# CAN_ProtoBoard_home_th.net
KiCad netlist of a schematic drawn in EAGLE
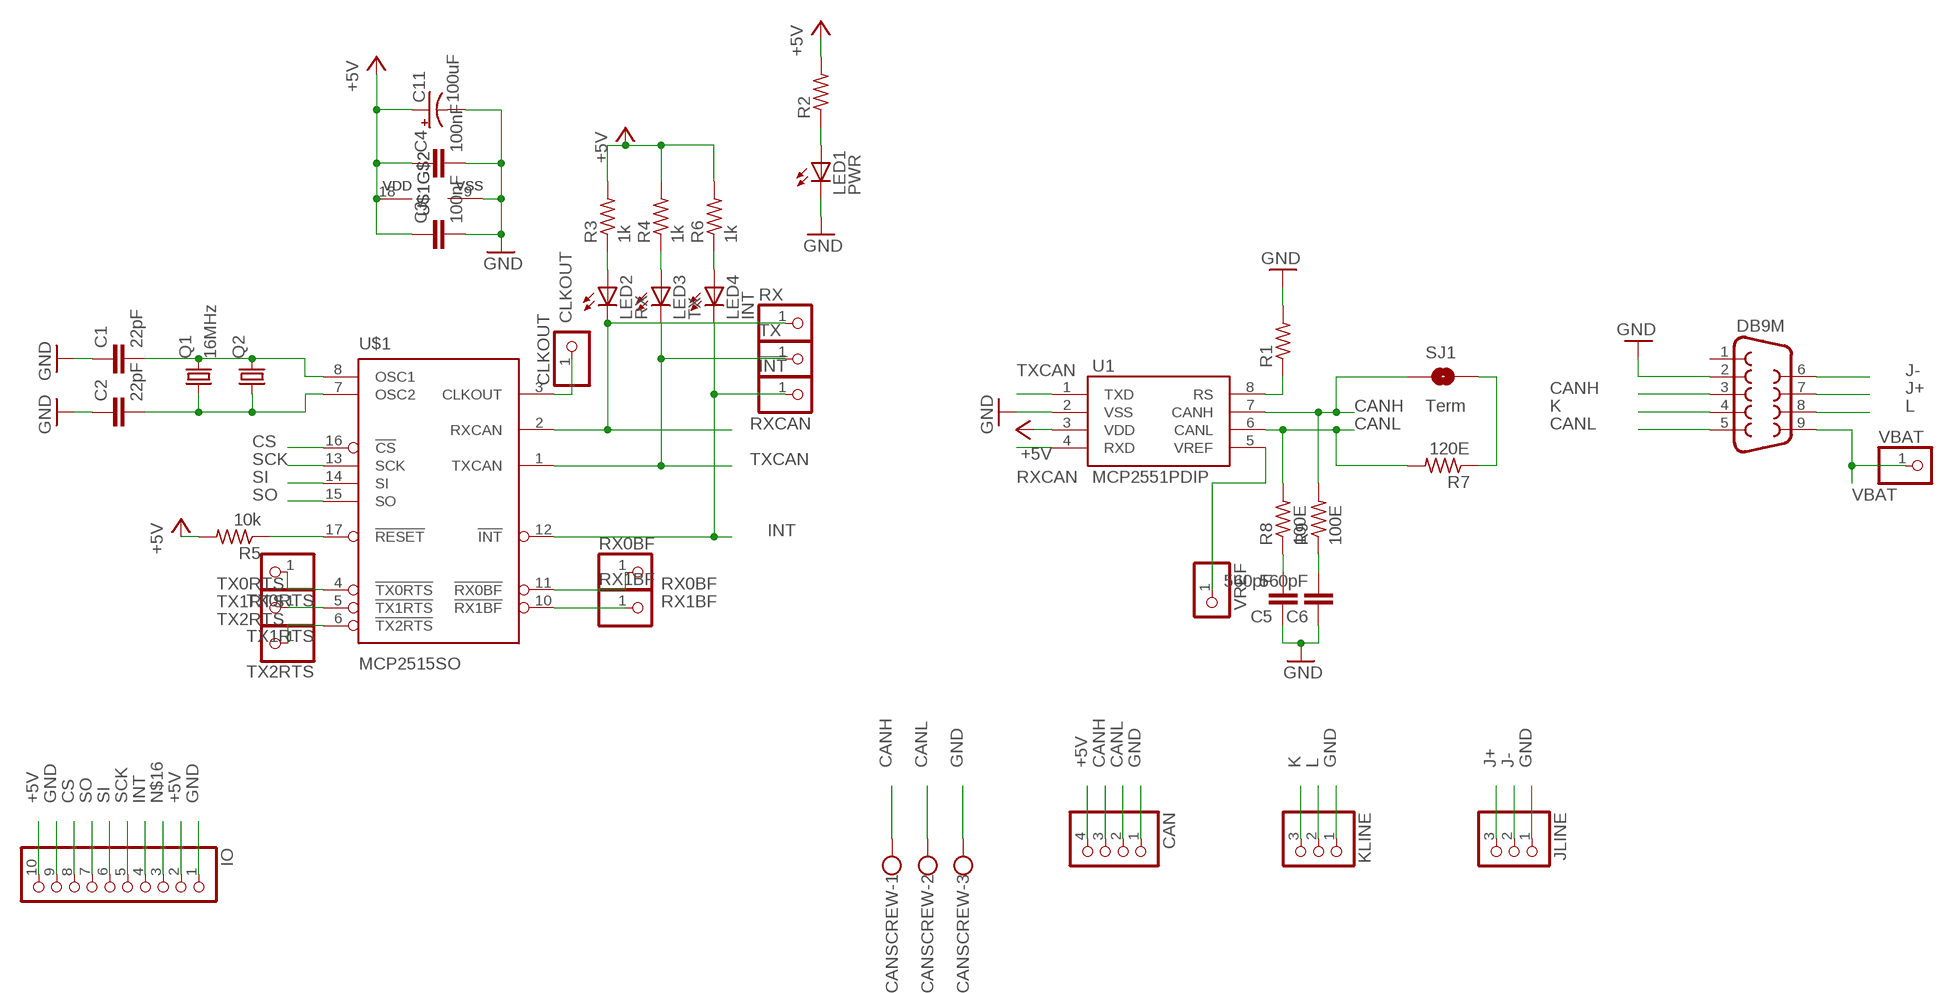
[diagram p0: schematic, sheet 1]

(export (version "E")
  (design (tool "Eeschema 10.0.6"))
  (components
    (comp (ref "!INT")
      (value "PINHD-1X1")
      (footprint "eagle-import:1X01")
      (libsource (lib "eagle-import") (part "PINHD-1X1"))
    )
    (comp (ref "C1")
      (value "22pF")
      (footprint "eagle-import:C0805K")
      (libsource (lib "eagle-import") (part "C-EUC0805K"))
    )
    (comp (ref "C2")
      (value "22pF")
      (footprint "eagle-import:C0805K")
      (libsource (lib "eagle-import") (part "C-EUC0805K"))
    )
    (comp (ref "C3")
      (value "100nF")
      (footprint "eagle-import:C0805K")
      (libsource (lib "eagle-import") (part "C-EUC0805K"))
    )
    (comp (ref "C4")
      (value "100nF")
      (footprint "eagle-import:C0805K")
      (libsource (lib "eagle-import") (part "C-EUC0805K"))
    )
    (comp (ref "C5")
      (value "560pF")
      (footprint "eagle-import:C0805K")
      (libsource (lib "eagle-import") (part "C-EUC0805K"))
    )
    (comp (ref "C6")
      (value "560pF")
      (footprint "eagle-import:C0805K")
      (libsource (lib "eagle-import") (part "C-EUC0805K"))
    )
    (comp (ref "C11")
      (value "100uF")
      (footprint "eagle-import:PANASONIC_D")
      (libsource (lib "eagle-import") (part "CPOL-USD"))
    )
    (comp (ref "CAN")
      (value "PINHD-1X4")
      (footprint "eagle-import:1X04")
      (libsource (lib "eagle-import") (part "PINHD-1X4"))
    )
    (comp (ref "CANSCREW")
      (value "W237-103")
      (footprint "eagle-import:W237-103")
      (fields (field (name "MPN") "237-103"))
      (libsource (lib "eagle-import") (part "W237-103"))
    )
    (comp (ref "CLKOUT")
      (value "PINHD-1X1")
      (footprint "eagle-import:1X01")
      (libsource (lib "eagle-import") (part "PINHD-1X1"))
    )
    (comp (ref "DB9M")
      (value "DB9MALE")
      (footprint "eagle-import:DB9_MALE")
      (libsource (lib "eagle-import") (part "DB9MALE"))
    )
    (comp (ref "IO")
      (value "PINHD-1X10")
      (footprint "eagle-import:1X10")
      (libsource (lib "eagle-import") (part "PINHD-1X10"))
    )
    (comp (ref "JLINE")
      (value "PINHD-1X3")
      (footprint "eagle-import:1X03")
      (libsource (lib "eagle-import") (part "PINHD-1X3"))
    )
    (comp (ref "KLINE")
      (value "PINHD-1X3")
      (footprint "eagle-import:1X03")
      (libsource (lib "eagle-import") (part "PINHD-1X3"))
    )
    (comp (ref "LED1")
      (value "PWR")
      (footprint "eagle-import:CHIPLED_0805")
      (libsource (lib "eagle-import") (part "LEDCHIPLED_0805"))
    )
    (comp (ref "LED2")
      (value "RX")
      (footprint "eagle-import:CHIPLED_0805")
      (libsource (lib "eagle-import") (part "LEDCHIPLED_0805"))
    )
    (comp (ref "LED3")
      (value "TX")
      (footprint "eagle-import:CHIPLED_0805")
      (libsource (lib "eagle-import") (part "LEDCHIPLED_0805"))
    )
    (comp (ref "LED4")
      (value "INT")
      (footprint "eagle-import:CHIPLED_0805")
      (libsource (lib "eagle-import") (part "LEDCHIPLED_0805"))
    )
    (comp (ref "Q1")
      (value "16MHz")
      (footprint "eagle-import:HC49_S")
      (libsource (lib "eagle-import") (part "CRYSTALHC49S"))
    )
    (comp (ref "Q2")
      (value "CRYSTALHC49UP")
      (footprint "eagle-import:HC49UP")
      (libsource (lib "eagle-import") (part "CRYSTALHC49UP"))
    )
    (comp (ref "R1")
      (value "R-US_R0805")
      (footprint "eagle-import:R0805")
      (libsource (lib "eagle-import") (part "R-US_R0805"))
    )
    (comp (ref "R2")
      (value "R-US_R0805")
      (footprint "eagle-import:R0805")
      (libsource (lib "eagle-import") (part "R-US_R0805"))
    )
    (comp (ref "R3")
      (value "1k")
      (footprint "eagle-import:R0805")
      (libsource (lib "eagle-import") (part "R-US_R0805"))
    )
    (comp (ref "R4")
      (value "1k")
      (footprint "eagle-import:R0805")
      (libsource (lib "eagle-import") (part "R-US_R0805"))
    )
    (comp (ref "R5")
      (value "10k")
      (footprint "eagle-import:R0805")
      (libsource (lib "eagle-import") (part "R-US_R0805"))
    )
    (comp (ref "R6")
      (value "1k")
      (footprint "eagle-import:R0805")
      (libsource (lib "eagle-import") (part "R-US_R0805"))
    )
    (comp (ref "R7")
      (value "120E")
      (footprint "eagle-import:R0805")
      (libsource (lib "eagle-import") (part "R-US_R0805"))
    )
    (comp (ref "R8")
      (value "100E")
      (footprint "eagle-import:R0805")
      (libsource (lib "eagle-import") (part "R-US_R0805"))
    )
    (comp (ref "R9")
      (value "100E")
      (footprint "eagle-import:R0805")
      (libsource (lib "eagle-import") (part "R-US_R0805"))
    )
    (comp (ref "RX")
      (value "PINHD-1X1")
      (footprint "eagle-import:1X01")
      (libsource (lib "eagle-import") (part "PINHD-1X1"))
    )
    (comp (ref "RX0BF")
      (value "PINHD-1X1")
      (footprint "eagle-import:1X01")
      (libsource (lib "eagle-import") (part "PINHD-1X1"))
    )
    (comp (ref "RX1BF")
      (value "PINHD-1X1")
      (footprint "eagle-import:1X01")
      (libsource (lib "eagle-import") (part "PINHD-1X1"))
    )
    (comp (ref "SJ1")
      (value "Term")
      (footprint "eagle-import:SJ_2S-TRACE")
      (libsource (lib "eagle-import") (part "SOLDERJUMPERTRACE"))
    )
    (comp (ref "TX")
      (value "PINHD-1X1")
      (footprint "eagle-import:1X01")
      (libsource (lib "eagle-import") (part "PINHD-1X1"))
    )
    (comp (ref "TX0RTS")
      (value "PINHD-1X1")
      (footprint "eagle-import:1X01")
      (libsource (lib "eagle-import") (part "PINHD-1X1"))
    )
    (comp (ref "TX1RTS")
      (value "PINHD-1X1")
      (footprint "eagle-import:1X01")
      (libsource (lib "eagle-import") (part "PINHD-1X1"))
    )
    (comp (ref "TX2RTS")
      (value "PINHD-1X1")
      (footprint "eagle-import:1X01")
      (libsource (lib "eagle-import") (part "PINHD-1X1"))
    )
    (comp (ref "U$1")
      (value "MCP2515SO")
      (footprint "eagle-import:SO-18W")
      (libsource (lib "eagle-import") (part "MCP2515SO"))
    )
    (comp (ref "U1")
      (value "MCP2551PDIP")
      (footprint "eagle-import:DIL08")
      (libsource (lib "eagle-import") (part "MCP2551PDIP"))
    )
    (comp (ref "VBAT")
      (value "PINHD-1X1")
      (footprint "eagle-import:1X01")
      (libsource (lib "eagle-import") (part "PINHD-1X1"))
    )
    (comp (ref "VREF")
      (value "PINHD-1X1")
      (footprint "eagle-import:1X01")
      (libsource (lib "eagle-import") (part "PINHD-1X1"))
    )
  )
  (nets
    (net (code "1") (name "+5V") (class "Default")
      (node (ref "C11") (pin "+") (pinfunction "+_+") (pintype "passive"))
      (node (ref "C3") (pin "1") (pinfunction "1_1") (pintype "passive"))
      (node (ref "C4") (pin "1") (pinfunction "1_1") (pintype "passive"))
      (node (ref "CAN") (pin "4") (pinfunction "4_4") (pintype "passive"))
      (node (ref "IO") (pin "10") (pinfunction "10_10") (pintype "passive"))
      (node (ref "IO") (pin "2") (pinfunction "2_2") (pintype "passive"))
      (node (ref "R2") (pin "2") (pinfunction "2_2") (pintype "passive"))
      (node (ref "R3") (pin "2") (pinfunction "2_2") (pintype "passive"))
      (node (ref "R4") (pin "2") (pinfunction "2_2") (pintype "passive"))
      (node (ref "R5") (pin "2") (pinfunction "2_2") (pintype "passive"))
      (node (ref "R6") (pin "2") (pinfunction "2_2") (pintype "passive"))
      (node (ref "U$1") (pin "18") (pinfunction "VDD_18") (pintype "power_in"))
      (node (ref "U1") (pin "3") (pinfunction "VDD_3") (pintype "bidirectional"))
    )
    (net (code "2") (name "/CANH") (class "Default")
      (node (ref "CAN") (pin "3") (pinfunction "3_3") (pintype "passive"))
      (node (ref "CANSCREW") (pin "1") (pinfunction "KL_1") (pintype "passive"))
      (node (ref "DB9M") (pin "3") (pinfunction "3_3") (pintype "passive"))
      (node (ref "R9") (pin "2") (pinfunction "2_2") (pintype "passive"))
      (node (ref "SJ1") (pin "1") (pinfunction "1_1") (pintype "passive"))
      (node (ref "U1") (pin "7") (pinfunction "CANH_7") (pintype "bidirectional"))
    )
    (net (code "3") (name "/CANL") (class "Default")
      (node (ref "CAN") (pin "2") (pinfunction "2_2") (pintype "passive"))
      (node (ref "CANSCREW") (pin "2") (pinfunction "KL_2") (pintype "passive"))
      (node (ref "DB9M") (pin "5") (pinfunction "5_5") (pintype "passive"))
      (node (ref "R7") (pin "2") (pinfunction "2_2") (pintype "passive"))
      (node (ref "R8") (pin "2") (pinfunction "2_2") (pintype "passive"))
      (node (ref "U1") (pin "6") (pinfunction "CANL_6") (pintype "bidirectional"))
    )
    (net (code "4") (name "/CLKOUT") (class "Default")
      (node (ref "CLKOUT") (pin "1") (pinfunction "1_1") (pintype "passive"))
      (node (ref "U$1") (pin "3") (pinfunction "CLKOUT_3") (pintype "output"))
    )
    (net (code "5") (name "/CS") (class "Default")
      (node (ref "IO") (pin "8") (pinfunction "8_8") (pintype "passive"))
      (node (ref "U$1") (pin "16") (pinfunction "~{CS}_16") (pintype "input"))
    )
    (net (code "6") (name "/INT") (class "Default")
      (node (ref "!INT") (pin "1") (pinfunction "1_1") (pintype "passive"))
      (node (ref "IO") (pin "4") (pinfunction "4_4") (pintype "passive"))
      (node (ref "LED4") (pin "C") (pinfunction "C_C") (pintype "passive"))
      (node (ref "U$1") (pin "12") (pinfunction "~{INT}_12") (pintype "output"))
    )
    (net (code "7") (name "/J+") (class "Default")
      (node (ref "DB9M") (pin "7") (pinfunction "7_7") (pintype "passive"))
      (node (ref "JLINE") (pin "3") (pinfunction "3_3") (pintype "passive"))
    )
    (net (code "8") (name "/J-") (class "Default")
      (node (ref "DB9M") (pin "6") (pinfunction "6_6") (pintype "passive"))
      (node (ref "JLINE") (pin "2") (pinfunction "2_2") (pintype "passive"))
    )
    (net (code "9") (name "/K") (class "Default")
      (node (ref "DB9M") (pin "4") (pinfunction "4_4") (pintype "passive"))
      (node (ref "KLINE") (pin "3") (pinfunction "3_3") (pintype "passive"))
    )
    (net (code "10") (name "/L") (class "Default")
      (node (ref "DB9M") (pin "8") (pinfunction "8_8") (pintype "passive"))
      (node (ref "KLINE") (pin "2") (pinfunction "2_2") (pintype "passive"))
    )
    (net (code "11") (name "/N$16") (class "Default")
      (node (ref "IO") (pin "3") (pinfunction "3_3") (pintype "passive"))
    )
    (net (code "12") (name "/RX0BF") (class "Default")
      (node (ref "RX0BF") (pin "1") (pinfunction "1_1") (pintype "passive"))
      (node (ref "U$1") (pin "11") (pinfunction "~{RX0BF}_11") (pintype "output"))
    )
    (net (code "13") (name "/RX1BF") (class "Default")
      (node (ref "RX1BF") (pin "1") (pinfunction "1_1") (pintype "passive"))
      (node (ref "U$1") (pin "10") (pinfunction "~{RX1BF}_10") (pintype "output"))
    )
    (net (code "14") (name "/RXCAN") (class "Default")
      (node (ref "LED2") (pin "C") (pinfunction "C_C") (pintype "passive"))
      (node (ref "RX") (pin "1") (pinfunction "1_1") (pintype "passive"))
      (node (ref "U$1") (pin "2") (pinfunction "RXCAN_2") (pintype "input"))
      (node (ref "U1") (pin "4") (pinfunction "RXD_4") (pintype "bidirectional"))
    )
    (net (code "15") (name "/SCK") (class "Default")
      (node (ref "IO") (pin "5") (pinfunction "5_5") (pintype "passive"))
      (node (ref "U$1") (pin "13") (pinfunction "SCK_13") (pintype "input"))
    )
    (net (code "16") (name "/SI") (class "Default")
      (node (ref "IO") (pin "6") (pinfunction "6_6") (pintype "passive"))
      (node (ref "U$1") (pin "14") (pinfunction "SI_14") (pintype "input"))
    )
    (net (code "17") (name "/SO") (class "Default")
      (node (ref "IO") (pin "7") (pinfunction "7_7") (pintype "passive"))
      (node (ref "U$1") (pin "15") (pinfunction "SO_15") (pintype "output"))
    )
    (net (code "18") (name "/TX0RTS") (class "Default")
      (node (ref "TX0RTS") (pin "1") (pinfunction "1_1") (pintype "passive"))
      (node (ref "U$1") (pin "4") (pinfunction "~{TX0RTS}_4") (pintype "input"))
    )
    (net (code "19") (name "/TX1RTS") (class "Default")
      (node (ref "TX1RTS") (pin "1") (pinfunction "1_1") (pintype "passive"))
      (node (ref "U$1") (pin "5") (pinfunction "~{TX1RTS}_5") (pintype "input"))
    )
    (net (code "20") (name "/TX2RTS") (class "Default")
      (node (ref "TX2RTS") (pin "1") (pinfunction "1_1") (pintype "passive"))
      (node (ref "U$1") (pin "6") (pinfunction "~{TX2RTS}_6") (pintype "input"))
    )
    (net (code "21") (name "/TXCAN") (class "Default")
      (node (ref "LED3") (pin "C") (pinfunction "C_C") (pintype "passive"))
      (node (ref "TX") (pin "1") (pinfunction "1_1") (pintype "passive"))
      (node (ref "U$1") (pin "1") (pinfunction "TXCAN_1") (pintype "output"))
      (node (ref "U1") (pin "1") (pinfunction "TXD_1") (pintype "bidirectional"))
    )
    (net (code "22") (name "/VBAT") (class "Default")
      (node (ref "DB9M") (pin "9") (pinfunction "9_9") (pintype "passive"))
      (node (ref "VBAT") (pin "1") (pinfunction "1_1") (pintype "passive"))
    )
    (net (code "23") (name "GND") (class "Default")
      (node (ref "C1") (pin "1") (pinfunction "1_1") (pintype "passive"))
      (node (ref "C11") (pin "-") (pinfunction "-_-") (pintype "passive"))
      (node (ref "C2") (pin "1") (pinfunction "1_1") (pintype "passive"))
      (node (ref "C3") (pin "2") (pinfunction "2_2") (pintype "passive"))
      (node (ref "C4") (pin "2") (pinfunction "2_2") (pintype "passive"))
      (node (ref "C5") (pin "1") (pinfunction "1_1") (pintype "passive"))
      (node (ref "C6") (pin "1") (pinfunction "1_1") (pintype "passive"))
      (node (ref "CAN") (pin "1") (pinfunction "1_1") (pintype "passive"))
      (node (ref "CANSCREW") (pin "3") (pinfunction "KL_3") (pintype "passive"))
      (node (ref "DB9M") (pin "2") (pinfunction "2_2") (pintype "passive"))
      (node (ref "IO") (pin "1") (pinfunction "1_1") (pintype "passive"))
      (node (ref "IO") (pin "9") (pinfunction "9_9") (pintype "passive"))
      (node (ref "JLINE") (pin "1") (pinfunction "1_1") (pintype "passive"))
      (node (ref "KLINE") (pin "1") (pinfunction "1_1") (pintype "passive"))
      (node (ref "LED1") (pin "C") (pinfunction "C_C") (pintype "passive"))
      (node (ref "R1") (pin "2") (pinfunction "2_2") (pintype "passive"))
      (node (ref "U$1") (pin "9") (pinfunction "VSS_9") (pintype "power_in"))
      (node (ref "U1") (pin "2") (pinfunction "VSS_2") (pintype "bidirectional"))
    )
    (net (code "24") (name "Net-(C5-Pad2)") (class "Default")
      (node (ref "C5") (pin "2") (pinfunction "2_2") (pintype "passive"))
      (node (ref "R8") (pin "1") (pinfunction "1_1") (pintype "passive"))
    )
    (net (code "25") (name "Net-(C6-Pad2)") (class "Default")
      (node (ref "C6") (pin "2") (pinfunction "2_2") (pintype "passive"))
      (node (ref "R9") (pin "1") (pinfunction "1_1") (pintype "passive"))
    )
    (net (code "26") (name "Net-(LED1-PadA)") (class "Default")
      (node (ref "LED1") (pin "A") (pinfunction "A_A") (pintype "passive"))
      (node (ref "R2") (pin "1") (pinfunction "1_1") (pintype "passive"))
    )
    (net (code "27") (name "Net-(LED2-PadA)") (class "Default")
      (node (ref "LED2") (pin "A") (pinfunction "A_A") (pintype "passive"))
      (node (ref "R3") (pin "1") (pinfunction "1_1") (pintype "passive"))
    )
    (net (code "28") (name "Net-(LED3-PadA)") (class "Default")
      (node (ref "LED3") (pin "A") (pinfunction "A_A") (pintype "passive"))
      (node (ref "R4") (pin "1") (pinfunction "1_1") (pintype "passive"))
    )
    (net (code "29") (name "Net-(LED4-PadA)") (class "Default")
      (node (ref "LED4") (pin "A") (pinfunction "A_A") (pintype "passive"))
      (node (ref "R6") (pin "1") (pinfunction "1_1") (pintype "passive"))
    )
    (net (code "30") (name "Net-(R7-Pad1)") (class "Default")
      (node (ref "R7") (pin "1") (pinfunction "1_1") (pintype "passive"))
      (node (ref "SJ1") (pin "2") (pinfunction "2_2") (pintype "passive"))
    )
    (net (code "31") (name "Net-(U$1A-OSC1)") (class "Default")
      (node (ref "C1") (pin "2") (pinfunction "2_2") (pintype "passive"))
      (node (ref "Q1") (pin "2") (pinfunction "2_2") (pintype "passive"))
      (node (ref "Q2") (pin "2") (pinfunction "2_2") (pintype "passive"))
      (node (ref "U$1") (pin "8") (pinfunction "OSC1_8") (pintype "input"))
    )
    (net (code "32") (name "Net-(U$1A-OSC2)") (class "Default")
      (node (ref "C2") (pin "2") (pinfunction "2_2") (pintype "passive"))
      (node (ref "Q1") (pin "1") (pinfunction "1_1") (pintype "passive"))
      (node (ref "Q2") (pin "1") (pinfunction "1_1") (pintype "passive"))
      (node (ref "U$1") (pin "7") (pinfunction "OSC2_7") (pintype "output"))
    )
    (net (code "33") (name "Net-(U$1A-~{RESET})") (class "Default")
      (node (ref "R5") (pin "1") (pinfunction "1_1") (pintype "passive"))
      (node (ref "U$1") (pin "17") (pinfunction "~{RESET}_17") (pintype "input"))
    )
    (net (code "34") (name "Net-(U1-RS)") (class "Default")
      (node (ref "R1") (pin "1") (pinfunction "1_1") (pintype "passive"))
      (node (ref "U1") (pin "8") (pinfunction "RS_8") (pintype "bidirectional"))
    )
    (net (code "35") (name "Net-(U1-VREF)") (class "Default")
      (node (ref "U1") (pin "5") (pinfunction "VREF_5") (pintype "bidirectional"))
      (node (ref "VREF") (pin "1") (pinfunction "1_1") (pintype "passive"))
    )
    (net (code "36") (name "unconnected-(DB9M-Pad1)") (class "Default")
      (node (ref "DB9M") (pin "1") (pinfunction "1_1") (pintype "passive"))
    )
  )
)
